# PCB_NON-CONTACT-THERMOMETER.net
KiCad netlist of a schematic drawn in Altium Designer
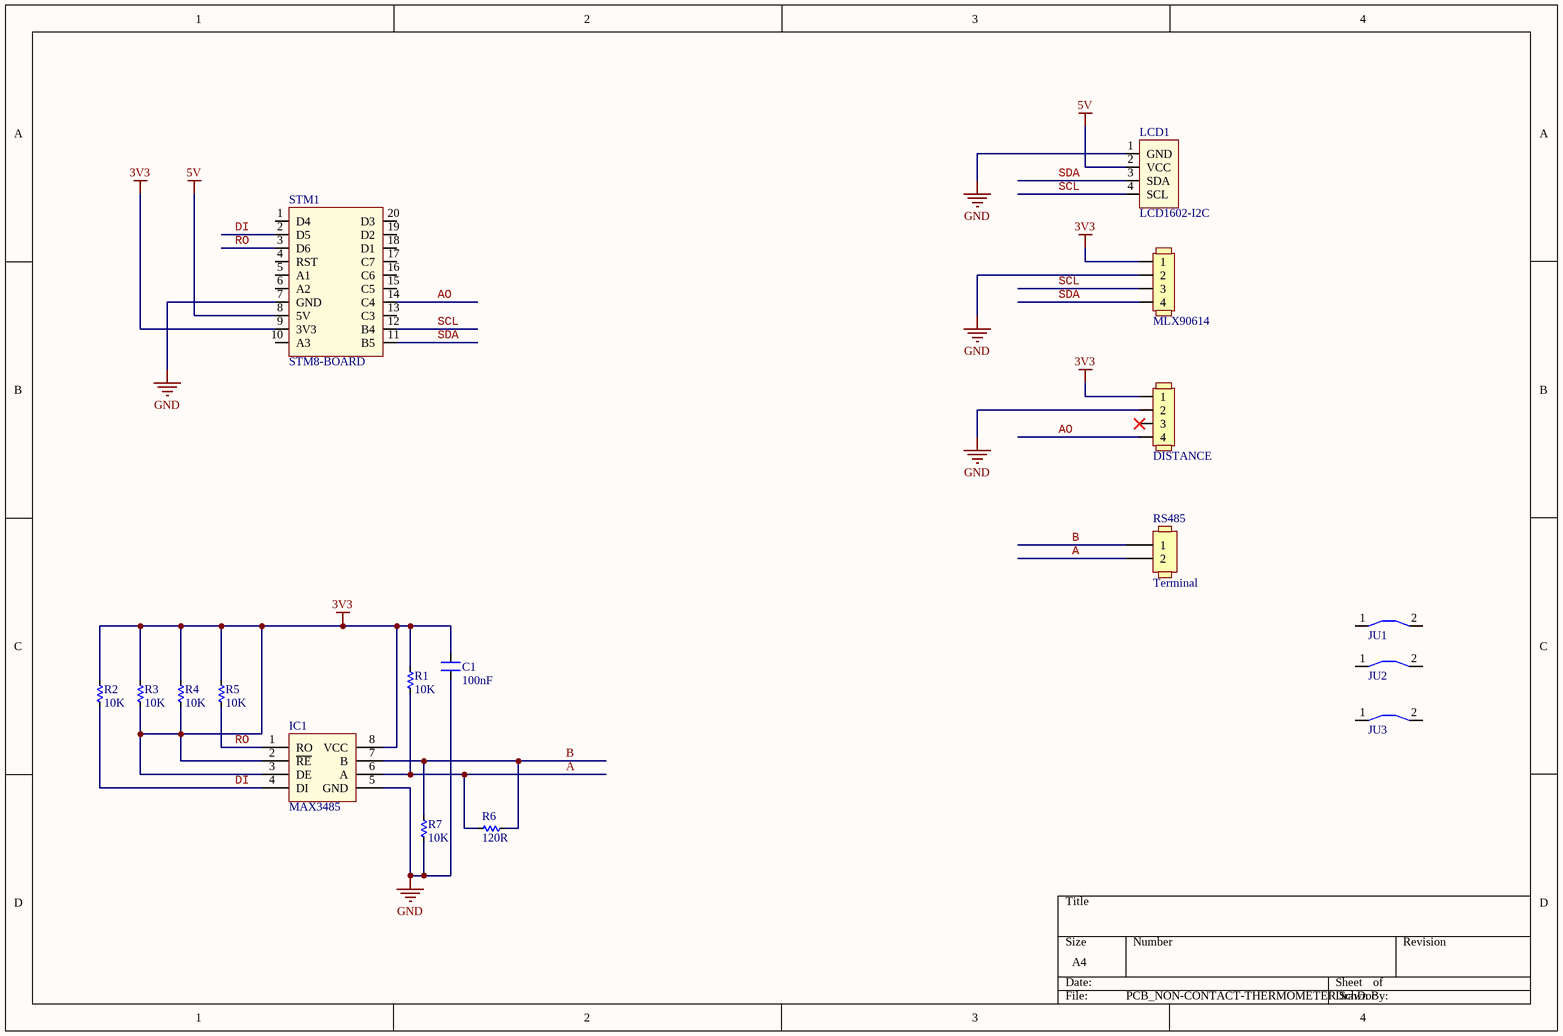
[diagram p0: PCB_NON-CONTACT-THERMOMETER.SchDoc]

(export (version "E")
  (design (tool "Eeschema 10.0.6"))
  (components
    (comp (ref "C1") (value "100nF") (footprint "CN1.5") (libsource (lib "LIBRARY_MuaLinhKien") (part "CN")))
    (comp (ref "DISTANCE")
      (value "Header 4")
      (footprint "HEADER x4")
      (libsource (lib "Duc") (part "Header 4"))
    )
    (comp (ref "IC1")
      (value "MAX3485")
      (footprint "DIP8")
      (description "RS232 - RS485 (Same sn75176)")
      (libsource (lib "LIBRARY_MuaLinhKien") (part "MAX485"))
    )
    (comp (ref "JU1")
      (value "JUMPER")
      (footprint "JUMPER 15MM")
      (libsource (lib "tunaSchlib") (part "JUMPER"))
    )
    (comp (ref "JU2")
      (value "JUMPER")
      (footprint "JUMPER 5MM")
      (libsource (lib "tunaSchlib") (part "JUMPER"))
    )
    (comp (ref "JU3")
      (value "JUMPER")
      (footprint "JUMPER 5MM")
      (libsource (lib "tunaSchlib") (part "JUMPER"))
    )
    (comp (ref "LCD1")
      (value "LCD1602-I2C")
      (footprint "LCD1602-I2C")
      (libsource (lib "tunaSchlib") (part "LCD1602-I2C"))
    )
    (comp (ref "MLX90614")
      (value "Header 4")
      (footprint "HEADER x4")
      (libsource (lib "Duc") (part "Header 4"))
    )
    (comp (ref "R1")
      (value "10K")
      (footprint "RES-1/4W")
      (description "Res")
      (fields
        (field (name "MANUFACTURER") "Generic Components")
        (field (name "PUBLISHER") "Altium Hobart Technology Centre")
      )
      (libsource (lib "LIBRARY_MuaLinhKien") (part "Res"))
    )
    (comp (ref "R2")
      (value "10K")
      (footprint "RES-1/4W")
      (description "Res")
      (fields
        (field (name "MANUFACTURER") "Generic Components")
        (field (name "PUBLISHER") "Altium Hobart Technology Centre")
      )
      (libsource (lib "LIBRARY_MuaLinhKien") (part "Res"))
    )
    (comp (ref "R3")
      (value "10K")
      (footprint "RES-1/4W")
      (description "Res")
      (fields
        (field (name "MANUFACTURER") "Generic Components")
        (field (name "PUBLISHER") "Altium Hobart Technology Centre")
      )
      (libsource (lib "LIBRARY_MuaLinhKien") (part "Res"))
    )
    (comp (ref "R4")
      (value "10K")
      (footprint "RES-1/4W")
      (description "Res")
      (fields
        (field (name "MANUFACTURER") "Generic Components")
        (field (name "PUBLISHER") "Altium Hobart Technology Centre")
      )
      (libsource (lib "LIBRARY_MuaLinhKien") (part "Res"))
    )
    (comp (ref "R5")
      (value "10K")
      (footprint "RES-1/4W")
      (description "Res")
      (fields
        (field (name "MANUFACTURER") "Generic Components")
        (field (name "PUBLISHER") "Altium Hobart Technology Centre")
      )
      (libsource (lib "LIBRARY_MuaLinhKien") (part "Res"))
    )
    (comp (ref "R6")
      (value "120R")
      (footprint "RES-1/4W")
      (description "Res")
      (fields
        (field (name "MANUFACTURER") "Generic Components")
        (field (name "PUBLISHER") "Altium Hobart Technology Centre")
      )
      (libsource (lib "LIBRARY_MuaLinhKien") (part "Res"))
    )
    (comp (ref "R7")
      (value "10K")
      (footprint "RES-1/4W")
      (description "Res")
      (fields
        (field (name "MANUFACTURER") "Generic Components")
        (field (name "PUBLISHER") "Altium Hobart Technology Centre")
      )
      (libsource (lib "LIBRARY_MuaLinhKien") (part "Res"))
    )
    (comp (ref "RS485")
      (value "Terminal")
      (footprint "Terminal x2 5mm")
      (description "Terminal x2")
      (libsource (lib "Duc") (part "Terminal x2"))
    )
    (comp (ref "STM1")
      (value "STM8-BOARD")
      (footprint "STM8-BOARD")
      (libsource (lib "tunaSchlib") (part "STM8-BOARD"))
    )
  )
  (nets
    (net (code "1") (name "/A") (class "Default")
      (node (ref "IC1") (pin "6") (pinfunction "A_6") (pintype "passive"))
      (node (ref "R1") (pin "2") (pinfunction "2_2") (pintype "passive"))
      (node (ref "R6") (pin "1") (pinfunction "1_1") (pintype "passive"))
      (node (ref "RS485") (pin "2") (pinfunction "2_2") (pintype "passive"))
    )
    (net (code "2") (name "/AO") (class "Default")
      (node (ref "DISTANCE") (pin "4") (pinfunction "4_4") (pintype "passive"))
      (node (ref "STM1") (pin "14") (pinfunction "C4_14") (pintype "power_in"))
    )
    (net (code "3") (name "/B") (class "Default")
      (node (ref "IC1") (pin "7") (pinfunction "B_7") (pintype "passive"))
      (node (ref "R6") (pin "2") (pinfunction "2_2") (pintype "passive"))
      (node (ref "R7") (pin "1") (pinfunction "1_1") (pintype "passive"))
      (node (ref "RS485") (pin "1") (pinfunction "1_1") (pintype "passive"))
    )
    (net (code "4") (name "/DI") (class "Default")
      (node (ref "IC1") (pin "4") (pinfunction "DI_4") (pintype "passive"))
      (node (ref "R2") (pin "2") (pinfunction "2_2") (pintype "passive"))
      (node (ref "STM1") (pin "2") (pinfunction "D5_2") (pintype "power_in"))
    )
    (net (code "5") (name "/RO") (class "Default")
      (node (ref "IC1") (pin "1") (pinfunction "RO_1") (pintype "passive"))
      (node (ref "R5") (pin "2") (pinfunction "2_2") (pintype "passive"))
      (node (ref "STM1") (pin "3") (pinfunction "D6_3") (pintype "power_in"))
    )
    (net (code "6") (name "/SCL") (class "Default")
      (node (ref "LCD1") (pin "4") (pinfunction "SCL_4") (pintype "power_in"))
      (node (ref "MLX90614") (pin "3") (pinfunction "3_3") (pintype "passive"))
      (node (ref "STM1") (pin "12") (pinfunction "B4_12") (pintype "power_in"))
    )
    (net (code "7") (name "/SDA") (class "Default")
      (node (ref "LCD1") (pin "3") (pinfunction "SDA_3") (pintype "power_in"))
      (node (ref "MLX90614") (pin "4") (pinfunction "4_4") (pintype "passive"))
      (node (ref "STM1") (pin "11") (pinfunction "B5_11") (pintype "power_in"))
    )
    (net (code "8") (name "3V3") (class "Default")
      (node (ref "C1") (pin "2") (pinfunction "2_2") (pintype "passive"))
      (node (ref "DISTANCE") (pin "1") (pinfunction "1_1") (pintype "passive"))
      (node (ref "IC1") (pin "2") (pinfunction "~{RE}_2") (pintype "passive"))
      (node (ref "IC1") (pin "3") (pinfunction "DE_3") (pintype "passive"))
      (node (ref "IC1") (pin "8") (pinfunction "VCC_8") (pintype "passive"))
      (node (ref "MLX90614") (pin "1") (pinfunction "1_1") (pintype "passive"))
      (node (ref "R1") (pin "1") (pinfunction "1_1") (pintype "passive"))
      (node (ref "R2") (pin "1") (pinfunction "1_1") (pintype "passive"))
      (node (ref "R3") (pin "1") (pinfunction "1_1") (pintype "passive"))
      (node (ref "R3") (pin "2") (pinfunction "2_2") (pintype "passive"))
      (node (ref "R4") (pin "1") (pinfunction "1_1") (pintype "passive"))
      (node (ref "R4") (pin "2") (pinfunction "2_2") (pintype "passive"))
      (node (ref "R5") (pin "1") (pinfunction "1_1") (pintype "passive"))
      (node (ref "STM1") (pin "9") (pinfunction "3V3_9") (pintype "power_in"))
    )
    (net (code "9") (name "5V") (class "Default")
      (node (ref "LCD1") (pin "2") (pinfunction "VCC_2") (pintype "power_in"))
      (node (ref "STM1") (pin "8") (pinfunction "5V_8") (pintype "power_in"))
    )
    (net (code "10") (name "GND") (class "Default")
      (node (ref "C1") (pin "1") (pinfunction "1_1") (pintype "passive"))
      (node (ref "DISTANCE") (pin "2") (pinfunction "2_2") (pintype "passive"))
      (node (ref "IC1") (pin "5") (pinfunction "GND_5") (pintype "passive"))
      (node (ref "LCD1") (pin "1") (pinfunction "GND_1") (pintype "power_in"))
      (node (ref "MLX90614") (pin "2") (pinfunction "2_2") (pintype "passive"))
      (node (ref "R7") (pin "2") (pinfunction "2_2") (pintype "passive"))
      (node (ref "STM1") (pin "7") (pinfunction "GND_7") (pintype "power_in"))
    )
    (net (code "11") (name "unconnected-(DISTANCE-Pad3)") (class "Default")
      (node (ref "DISTANCE") (pin "3") (pinfunction "3_3") (pintype "passive+no_connect"))
    )
    (net (code "12") (name "unconnected-(JU1-Pad1)") (class "Default")
      (node (ref "JU1") (pin "1") (pinfunction "1_1") (pintype "power_in"))
    )
    (net (code "13") (name "unconnected-(JU1-Pad2)") (class "Default")
      (node (ref "JU1") (pin "2") (pinfunction "2_2") (pintype "power_in"))
    )
    (net (code "14") (name "unconnected-(JU2-Pad1)") (class "Default")
      (node (ref "JU2") (pin "1") (pinfunction "1_1") (pintype "power_in"))
    )
    (net (code "15") (name "unconnected-(JU2-Pad2)") (class "Default")
      (node (ref "JU2") (pin "2") (pinfunction "2_2") (pintype "power_in"))
    )
    (net (code "16") (name "unconnected-(JU3-Pad1)") (class "Default")
      (node (ref "JU3") (pin "1") (pinfunction "1_1") (pintype "power_in"))
    )
    (net (code "17") (name "unconnected-(JU3-Pad2)") (class "Default")
      (node (ref "JU3") (pin "2") (pinfunction "2_2") (pintype "power_in"))
    )
    (net (code "18") (name "unconnected-(STM1-A1-Pad5)") (class "Default")
      (node (ref "STM1") (pin "5") (pinfunction "A1_5") (pintype "power_in"))
    )
    (net (code "19") (name "unconnected-(STM1-A2-Pad6)") (class "Default")
      (node (ref "STM1") (pin "6") (pinfunction "A2_6") (pintype "power_in"))
    )
    (net (code "20") (name "unconnected-(STM1-A3-Pad10)") (class "Default")
      (node (ref "STM1") (pin "10") (pinfunction "A3_10") (pintype "power_in"))
    )
    (net (code "21") (name "unconnected-(STM1-C3-Pad13)") (class "Default")
      (node (ref "STM1") (pin "13") (pinfunction "C3_13") (pintype "power_in"))
    )
    (net (code "22") (name "unconnected-(STM1-C5-Pad15)") (class "Default")
      (node (ref "STM1") (pin "15") (pinfunction "C5_15") (pintype "power_in"))
    )
    (net (code "23") (name "unconnected-(STM1-C6-Pad16)") (class "Default")
      (node (ref "STM1") (pin "16") (pinfunction "C6_16") (pintype "power_in"))
    )
    (net (code "24") (name "unconnected-(STM1-C7-Pad17)") (class "Default")
      (node (ref "STM1") (pin "17") (pinfunction "C7_17") (pintype "power_in"))
    )
    (net (code "25") (name "unconnected-(STM1-D1-Pad18)") (class "Default")
      (node (ref "STM1") (pin "18") (pinfunction "D1_18") (pintype "power_in"))
    )
    (net (code "26") (name "unconnected-(STM1-D2-Pad19)") (class "Default")
      (node (ref "STM1") (pin "19") (pinfunction "D2_19") (pintype "power_in"))
    )
    (net (code "27") (name "unconnected-(STM1-D3-Pad20)") (class "Default")
      (node (ref "STM1") (pin "20") (pinfunction "D3_20") (pintype "power_in"))
    )
    (net (code "28") (name "unconnected-(STM1-D4-Pad1)") (class "Default")
      (node (ref "STM1") (pin "1") (pinfunction "D4_1") (pintype "power_in"))
    )
    (net (code "29") (name "unconnected-(STM1-RST-Pad4)") (class "Default")
      (node (ref "STM1") (pin "4") (pinfunction "RST_4") (pintype "power_in"))
    )
  )
)
